# Sheet1.net
KiCad netlist of a schematic drawn in Altium Designer
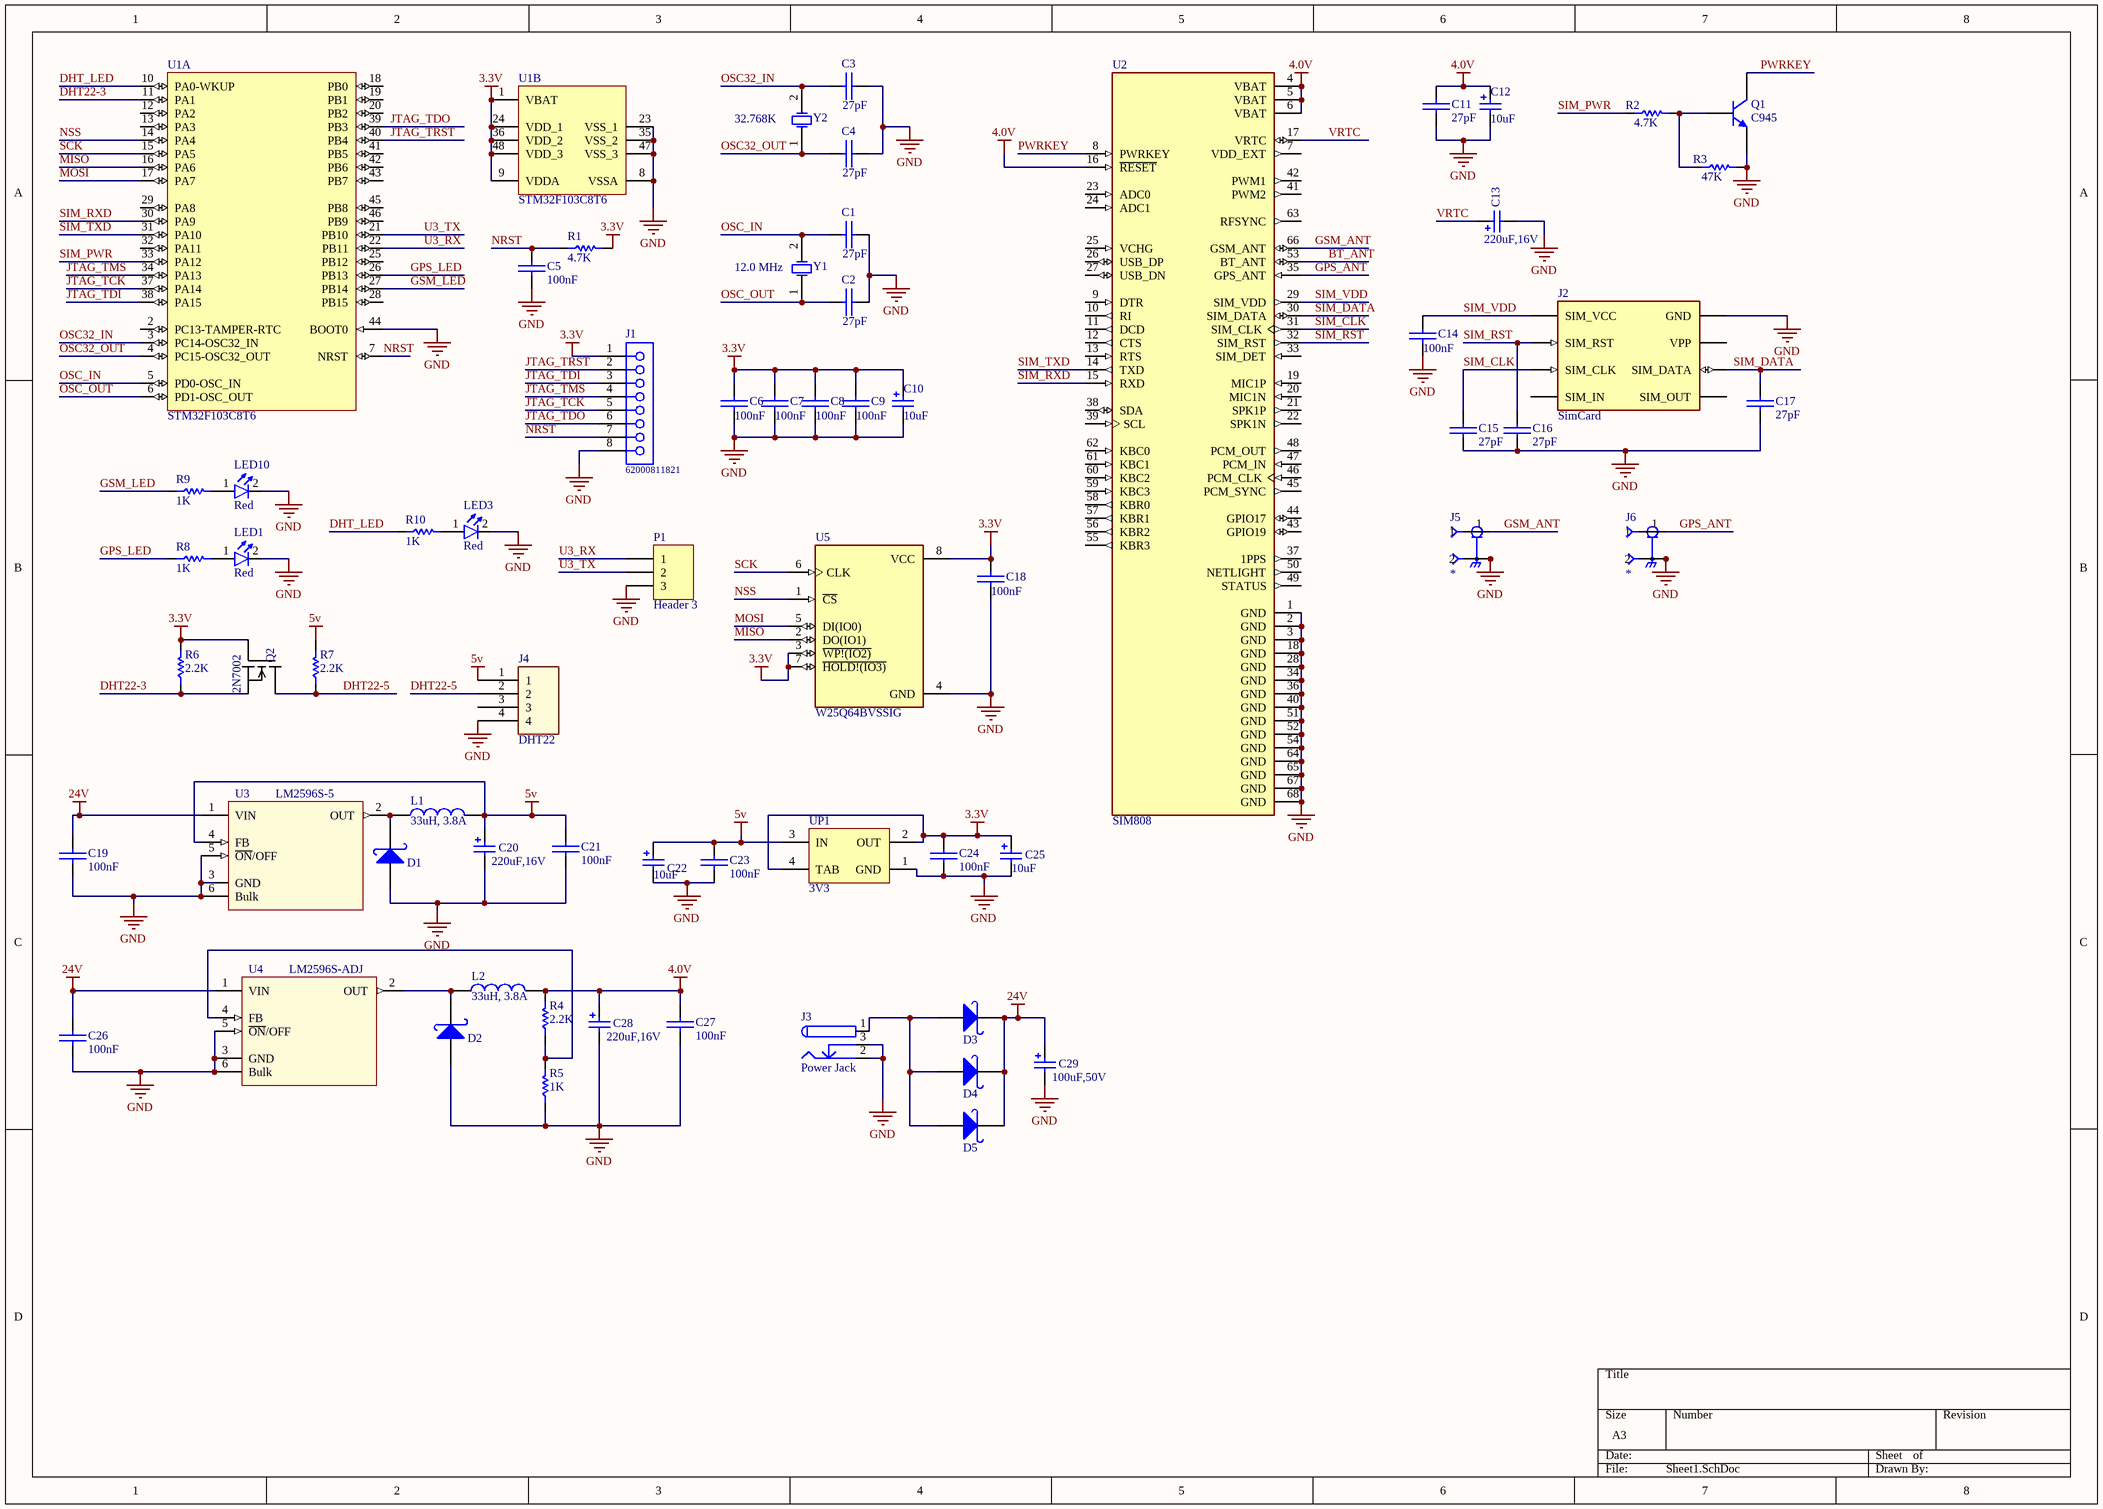
[diagram p0: Sheet1.SchDoc]

(export (version "E")
  (design (tool "Eeschema 10.0.6"))
  (components
    (comp (ref "C1")
      (value "27pF")
      (footprint "SMD_CAP_0805")
      (description "Bipolar Capacitor")
      (fields (field (name "VOLTAGE") "100V") (field (name "DESIGNER") "Saeid Jorablo"))
      (libsource (lib "My_Library") (part "Cap-Bipolar"))
    )
    (comp (ref "C2")
      (value "27pF")
      (footprint "SMD_CAP_0805")
      (description "Bipolar Capacitor")
      (fields (field (name "VOLTAGE") "100V") (field (name "DESIGNER") "Saeid Jorablo"))
      (libsource (lib "My_Library") (part "Cap-Bipolar"))
    )
    (comp (ref "C3")
      (value "27pF")
      (footprint "SMD_CAP_0805")
      (description "Bipolar Capacitor")
      (fields (field (name "VOLTAGE") "100V") (field (name "DESIGNER") "Saeid Jorablo"))
      (libsource (lib "My_Library") (part "Cap-Bipolar"))
    )
    (comp (ref "C4")
      (value "27pF")
      (footprint "SMD_CAP_0805")
      (description "Bipolar Capacitor")
      (fields (field (name "VOLTAGE") "100V") (field (name "DESIGNER") "Saeid Jorablo"))
      (libsource (lib "My_Library") (part "Cap-Bipolar"))
    )
    (comp (ref "C5")
      (value "100nF")
      (footprint "SMD_CAP_0805")
      (description "Bipolar Capacitor")
      (fields (field (name "VOLTAGE") "100V") (field (name "DESIGNER") "Saeid Jorablo"))
      (libsource (lib "My_Library") (part "Cap-Bipolar"))
    )
    (comp (ref "C6")
      (value "100nF")
      (footprint "SMD_CAP_0805")
      (description "Bipolar Capacitor")
      (fields (field (name "VOLTAGE") "100V") (field (name "DESIGNER") "Saeid Jorablo"))
      (libsource (lib "My_Library") (part "Cap-Bipolar"))
    )
    (comp (ref "C7")
      (value "100nF")
      (footprint "SMD_CAP_0805")
      (description "Bipolar Capacitor")
      (fields (field (name "VOLTAGE") "100V") (field (name "DESIGNER") "Saeid Jorablo"))
      (libsource (lib "My_Library") (part "Cap-Bipolar"))
    )
    (comp (ref "C8")
      (value "100nF")
      (footprint "SMD_CAP_0805")
      (description "Bipolar Capacitor")
      (fields (field (name "VOLTAGE") "100V") (field (name "DESIGNER") "Saeid Jorablo"))
      (libsource (lib "My_Library") (part "Cap-Bipolar"))
    )
    (comp (ref "C9")
      (value "100nF")
      (footprint "SMD_CAP_0805")
      (description "Bipolar Capacitor")
      (fields (field (name "VOLTAGE") "100V") (field (name "DESIGNER") "Saeid Jorablo"))
      (libsource (lib "My_Library") (part "Cap-Bipolar"))
    )
    (comp (ref "C10")
      (value "10uF")
      (footprint "WCAP-AS5H_4x5.5")
      (description "WCAP-AS5H SMT Aluminum Electrolytic Capacitors, D4mm x L5.5mm, 22uF, +/-20%, 6.3VDC")
      (fields (field (name "PART NUMBER") "865230140001") (field (name "PUBLISHER") "Wurth Elektronik"))
      (libsource (lib "Altium_WCAP-AS5H (rev19a)") (part "865230140001"))
    )
    (comp (ref "C11")
      (value "27pF")
      (footprint "SMD_CAP_0805")
      (description "Bipolar Capacitor")
      (fields (field (name "VOLTAGE") "100V") (field (name "DESIGNER") "Saeid Jorablo"))
      (libsource (lib "My_Library") (part "Cap-Bipolar"))
    )
    (comp (ref "C12")
      (value "10uF")
      (footprint "WCAP-AS5H_4x5.5")
      (description "WCAP-AS5H SMT Aluminum Electrolytic Capacitors, D4mm x L5.5mm, 22uF, +/-20%, 6.3VDC")
      (fields (field (name "PART NUMBER") "865230140001") (field (name "PUBLISHER") "Wurth Elektronik"))
      (libsource (lib "Altium_WCAP-AS5H (rev19a)") (part "865230140001"))
    )
    (comp (ref "C13")
      (value "220uF,16V")
      (footprint "WCAP-AS5H_6.3x7.7")
      (description "WCAP-AS5H SMT Aluminum Electrolytic Capacitors, D6.3mm x L7.7mm, 100uF, +/-20%, 16VDC")
      (fields (field (name "PART NUMBER") "865230345005") (field (name "PUBLISHER") "Wurth Elektronik"))
      (libsource (lib "Altium_WCAP-AS5H (rev19a)") (part "865230345005"))
    )
    (comp (ref "C14")
      (value "100nF")
      (footprint "SMD_CAP_0805")
      (description "Bipolar Capacitor")
      (fields (field (name "VOLTAGE") "100V") (field (name "DESIGNER") "Saeid Jorablo"))
      (libsource (lib "My_Library") (part "Cap-Bipolar"))
    )
    (comp (ref "C15")
      (value "27pF")
      (footprint "SMD_CAP_0805")
      (description "Bipolar Capacitor")
      (fields (field (name "VOLTAGE") "100V") (field (name "DESIGNER") "Saeid Jorablo"))
      (libsource (lib "My_Library") (part "Cap-Bipolar"))
    )
    (comp (ref "C16")
      (value "27pF")
      (footprint "SMD_CAP_0805")
      (description "Bipolar Capacitor")
      (fields (field (name "VOLTAGE") "100V") (field (name "DESIGNER") "Saeid Jorablo"))
      (libsource (lib "My_Library") (part "Cap-Bipolar"))
    )
    (comp (ref "C17")
      (value "27pF")
      (footprint "SMD_CAP_0805")
      (description "Bipolar Capacitor")
      (fields (field (name "VOLTAGE") "100V") (field (name "DESIGNER") "Saeid Jorablo"))
      (libsource (lib "My_Library") (part "Cap-Bipolar"))
    )
    (comp (ref "C18")
      (value "100nF")
      (footprint "SMD_CAP_0805")
      (description "Bipolar Capacitor")
      (fields (field (name "VOLTAGE") "100V") (field (name "DESIGNER") "Saeid Jorablo"))
      (libsource (lib "My_Library") (part "Cap-Bipolar"))
    )
    (comp (ref "C19")
      (value "100nF")
      (footprint "SMD_CAP_0805")
      (description "Bipolar Capacitor")
      (fields (field (name "VOLTAGE") "100V") (field (name "DESIGNER") "Saeid Jorablo"))
      (libsource (lib "My_Library") (part "Cap-Bipolar"))
    )
    (comp (ref "C20")
      (value "220uF,16V")
      (footprint "WCAP-AS5H_6.3x7.7")
      (description "WCAP-AS5H SMT Aluminum Electrolytic Capacitors, D6.3mm x L7.7mm, 100uF, +/-20%, 16VDC")
      (fields (field (name "PART NUMBER") "865230345005") (field (name "PUBLISHER") "Wurth Elektronik"))
      (libsource (lib "Altium_WCAP-AS5H (rev19a)") (part "865230345005"))
    )
    (comp (ref "C21")
      (value "100nF")
      (footprint "SMD_CAP_0805")
      (description "Bipolar Capacitor")
      (fields (field (name "VOLTAGE") "100V") (field (name "DESIGNER") "Saeid Jorablo"))
      (libsource (lib "My_Library") (part "Cap-Bipolar"))
    )
    (comp (ref "C22")
      (value "10uF")
      (footprint "WCAP-AS5H_4x5.5")
      (description "WCAP-AS5H SMT Aluminum Electrolytic Capacitors, D4mm x L5.5mm, 22uF, +/-20%, 6.3VDC")
      (fields (field (name "PART NUMBER") "865230140001") (field (name "PUBLISHER") "Wurth Elektronik"))
      (libsource (lib "Altium_WCAP-AS5H (rev19a)") (part "865230140001"))
    )
    (comp (ref "C23")
      (value "100nF")
      (footprint "SMD_CAP_0805")
      (description "Bipolar Capacitor")
      (fields (field (name "VOLTAGE") "100V") (field (name "DESIGNER") "Saeid Jorablo"))
      (libsource (lib "My_Library") (part "Cap-Bipolar"))
    )
    (comp (ref "C24")
      (value "100nF")
      (footprint "SMD_CAP_0805")
      (description "Bipolar Capacitor")
      (fields (field (name "VOLTAGE") "100V") (field (name "DESIGNER") "Saeid Jorablo"))
      (libsource (lib "My_Library") (part "Cap-Bipolar"))
    )
    (comp (ref "C25")
      (value "10uF")
      (footprint "WCAP-AS5H_4x5.5")
      (description "WCAP-AS5H SMT Aluminum Electrolytic Capacitors, D4mm x L5.5mm, 22uF, +/-20%, 6.3VDC")
      (fields (field (name "PART NUMBER") "865230140001") (field (name "PUBLISHER") "Wurth Elektronik"))
      (libsource (lib "Altium_WCAP-AS5H (rev19a)") (part "865230140001"))
    )
    (comp (ref "C26")
      (value "100nF")
      (footprint "SMD_CAP_0805")
      (description "Bipolar Capacitor")
      (fields (field (name "VOLTAGE") "100V") (field (name "DESIGNER") "Saeid Jorablo"))
      (libsource (lib "My_Library") (part "Cap-Bipolar"))
    )
    (comp (ref "C27")
      (value "100nF")
      (footprint "SMD_CAP_0805")
      (description "Bipolar Capacitor")
      (fields (field (name "VOLTAGE") "100V") (field (name "DESIGNER") "Saeid Jorablo"))
      (libsource (lib "My_Library") (part "Cap-Bipolar"))
    )
    (comp (ref "C28")
      (value "220uF,16V")
      (footprint "WCAP-AS5H_6.3x7.7")
      (description "WCAP-AS5H SMT Aluminum Electrolytic Capacitors, D6.3mm x L7.7mm, 100uF, +/-20%, 16VDC")
      (fields (field (name "PART NUMBER") "865230345005") (field (name "PUBLISHER") "Wurth Elektronik"))
      (libsource (lib "Altium_WCAP-AS5H (rev19a)") (part "865230345005"))
    )
    (comp (ref "C29")
      (value "100uF,50V")
      (footprint "WCAP-AS5H_8x10.5")
      (description "WCAP-AS5H SMT Aluminum Electrolytic Capacitors, D8mm x L10.5mm, 47uF, +/-20%, 50VDC")
      (fields (field (name "PART NUMBER") "865230653012") (field (name "PUBLISHER") "Wurth Elektronik"))
      (libsource (lib "Altium_WCAP-AS5H (rev19a)") (part "865230653012"))
    )
    (comp (ref "D1")
      (value "1n5822")
      (footprint "Diode 1N4007 SMD")
      (description "Schottky Rectifiers")
      (fields
        (field (name "MANUFACTURER") "ON Semiconductor/Fairchild")
        (field (name "DESIGNER") "Abbas Basereh")
      )
      (libsource (lib "Altium") (part "1N5822 SMD"))
    )
    (comp (ref "D2")
      (value "1n5822")
      (footprint "Diode 1N4007 SMD")
      (description "Schottky Rectifiers")
      (fields
        (field (name "MANUFACTURER") "ON Semiconductor/Fairchild")
        (field (name "DESIGNER") "Abbas Basereh")
      )
      (libsource (lib "Altium") (part "1N5822 SMD"))
    )
    (comp (ref "D3")
      (value "1n5822")
      (footprint "Diode 1N4007 SMD")
      (description "Schottky Rectifiers")
      (fields
        (field (name "MANUFACTURER") "ON Semiconductor/Fairchild")
        (field (name "DESIGNER") "Abbas Basereh")
      )
      (libsource (lib "Altium") (part "1N5822 SMD"))
    )
    (comp (ref "D4")
      (value "1n5822")
      (footprint "Diode 1N4007 SMD")
      (description "Schottky Rectifiers")
      (fields
        (field (name "MANUFACTURER") "ON Semiconductor/Fairchild")
        (field (name "DESIGNER") "Abbas Basereh")
      )
      (libsource (lib "Altium") (part "1N5822 SMD"))
    )
    (comp (ref "D5")
      (value "1n5822")
      (footprint "Diode 1N4007 SMD")
      (description "Schottky Rectifiers")
      (fields
        (field (name "MANUFACTURER") "ON Semiconductor/Fairchild")
        (field (name "DESIGNER") "Abbas Basereh")
      )
      (libsource (lib "Altium") (part "1N5822 SMD"))
    )
    (comp (ref "J1")
      (value "62000811821")
      (footprint "62000811821")
      (description "WR-PHD Socket Header, THT, pitch 2mm, Single Row, Vertical, 8pin")
      (fields (field (name "PUBLISHER") "Wurth Elektronik"))
      (libsource (lib "62000811121_Altium_WR-PHD_rev19a") (part "62000811821"))
    )
    (comp (ref "J2")
      (value "SimCard")
      (footprint "SImCArd")
      (libsource (lib "SimCard_Connector") (part "SimCard"))
    )
    (comp (ref "J3")
      (value "Power Jack")
      (footprint "Power Jack")
      (fields (field (name "DESIGNER") "Saeid Jorablo"))
      (libsource (lib "My_Library") (part "Power Jack"))
    )
    (comp (ref "J4")
      (value "DHT22")
      (footprint "XH-12-Right")
      (libsource (lib "ST-XH-4 pin_right") (part "XH-Connector-4pin-right"))
    )
    (comp (ref "J5")
      (value "221790-1")
      (footprint "TE_221790-1")
      (description "Connector; SMA; PCB; Right Angle; Stainless Steel; 0.6 in.; Beryllium Copper")
      (fields (field (name "MF") "TE Connectivity") (field (name "COMMENT_1") "*"))
      (libsource (lib "SMA_RightAngle") (part "221790-1"))
    )
    (comp (ref "J6")
      (value "221790-1")
      (footprint "TE_221790-1")
      (description "Connector; SMA; PCB; Right Angle; Stainless Steel; 0.6 in.; Beryllium Copper")
      (fields (field (name "MF") "TE Connectivity") (field (name "COMMENT_1") "*"))
      (libsource (lib "SMA_RightAngle") (part "221790-1"))
    )
    (comp (ref "L1")
      (value "33uH, 3.8A")
      (footprint "WE-PD_1210")
      (description "WE-PD SMT Power Inductor, size 1210, 47uH, 3.8A")
      (fields (field (name "PART NUMBER") "7447709470") (field (name "PUBLISHER") "Wurth Elektronik"))
      (libsource (lib "ALTIUM-WE-PD-rev19b") (part "7447709470"))
    )
    (comp (ref "L2")
      (value "33uH, 3.8A")
      (footprint "WE-PD_1210")
      (description "WE-PD SMT Power Inductor, size 1210, 47uH, 3.8A")
      (fields (field (name "PART NUMBER") "7447709470") (field (name "PUBLISHER") "Wurth Elektronik"))
      (libsource (lib "ALTIUM-WE-PD-rev19b") (part "7447709470"))
    )
    (comp (ref "LED1")
      (value "Red")
      (footprint "LED-3mm")
      (description "LED")
      (fields (field (name "COLOR") "Red") (field (name "DESIGNER") "Saeid Jorablo"))
      (libsource (lib "My_Library") (part "LED"))
    )
    (comp (ref "LED3")
      (value "Red")
      (footprint "LED-3mm")
      (description "LED")
      (fields (field (name "COLOR") "Red") (field (name "DESIGNER") "Saeid Jorablo"))
      (libsource (lib "My_Library") (part "LED"))
    )
    (comp (ref "LED10")
      (value "Red")
      (footprint "LED-3mm")
      (description "LED")
      (fields (field (name "COLOR") "Red") (field (name "DESIGNER") "Saeid Jorablo"))
      (libsource (lib "My_Library") (part "LED"))
    )
    (comp (ref "P1")
      (value "Header 3")
      (footprint "HDR1X3")
      (description "Header, 3-Pin")
      (fields (field (name "PUBLISHER") "Altium Limited"))
      (libsource (lib "Altium") (part "Header 3"))
    )
    (comp (ref "Q1")
      (value "C945")
      (footprint "SOT23_N")
      (description "NPN Silicon Epitaxial Planar Transistor")
      (fields (field (name "PUBLISHER") "Abbas Basereh"))
      (libsource (lib "Altium") (part "C945"))
    )
    (comp (ref "Q2")
      (value "2N7002")
      (footprint "*SOT23")
      (description "Transistor NPN Mos 2N7002 SILICONIX miliampere=100 V=60 SOt23")
      (fields (field (name "MF") "STMicroelectronics"))
      (libsource (lib "2N7002") (part "2N7002"))
    )
    (comp (ref "R1")
      (value "4.7K")
      (footprint "RES 0805 (2012X06L)")
      (description "Resistor")
      (fields (field (name "TOLERANCE") "5%") (field (name "POWER") "1/8 W"))
      (libsource (lib "My_Library") (part "Resistor"))
    )
    (comp (ref "R2")
      (value "4.7K")
      (footprint "RES 0805 (2012X06L)")
      (description "Resistor")
      (fields (field (name "TOLERANCE") "5%") (field (name "POWER") "1/8 W"))
      (libsource (lib "My_Library") (part "Resistor"))
    )
    (comp (ref "R3")
      (value "47K")
      (footprint "RES 0805 (2012X06L)")
      (description "Resistor")
      (fields (field (name "TOLERANCE") "5%") (field (name "POWER") "1/8 W"))
      (libsource (lib "My_Library") (part "Resistor"))
    )
    (comp (ref "R4")
      (value "2.2K")
      (footprint "RES 0805 (2012X06L)")
      (description "Resistor")
      (fields (field (name "TOLERANCE") "5%") (field (name "POWER") "1/8 W"))
      (libsource (lib "My_Library") (part "Resistor"))
    )
    (comp (ref "R5")
      (value "1K")
      (footprint "RES 0805 (2012X06L)")
      (description "Resistor")
      (fields (field (name "TOLERANCE") "5%") (field (name "POWER") "1/8 W"))
      (libsource (lib "My_Library") (part "Resistor"))
    )
    (comp (ref "R6")
      (value "2.2K")
      (footprint "RES 0805 (2012X06L)")
      (description "Resistor")
      (fields (field (name "TOLERANCE") "5%") (field (name "POWER") "1/8 W"))
      (libsource (lib "My_Library") (part "Resistor"))
    )
    (comp (ref "R7")
      (value "2.2K")
      (footprint "RES 0805 (2012X06L)")
      (description "Resistor")
      (fields (field (name "TOLERANCE") "5%") (field (name "POWER") "1/8 W"))
      (libsource (lib "My_Library") (part "Resistor"))
    )
    (comp (ref "R8")
      (value "1K")
      (footprint "RES 0805 (2012X06L)")
      (description "Resistor")
      (fields (field (name "TOLERANCE") "5%") (field (name "POWER") "1/8 W"))
      (libsource (lib "My_Library") (part "Resistor"))
    )
    (comp (ref "R9")
      (value "1K")
      (footprint "RES 0805 (2012X06L)")
      (description "Resistor")
      (fields (field (name "TOLERANCE") "5%") (field (name "POWER") "1/8 W"))
      (libsource (lib "My_Library") (part "Resistor"))
    )
    (comp (ref "R10")
      (value "1K")
      (footprint "RES 0805 (2012X06L)")
      (description "Resistor")
      (fields (field (name "TOLERANCE") "5%") (field (name "POWER") "1/8 W"))
      (libsource (lib "My_Library") (part "Resistor"))
    )
    (comp (ref "U1")
      (value "STM32F103C8T6")
      (footprint "STM-LQFP48_N")
      (libsource (lib "STMicroelectronics STM32 F1") (part "STM32F103C8T6"))
    )
    (comp (ref "U2")
      (value "SIM808")
      (footprint "XCVR_SIM808")
      (description "SIM808 GPS, GPRS/GSM RF Arduino Platform Evaluation Expansion Board")
      (fields (field (name "MF") "Adafruit Industries"))
      (libsource (lib "SIM_808") (part "SIM808"))
    )
    (comp (ref "U3")
      (value "LM2596S-5")
      (footprint "*TO170P1435X465-6N")
      (fields (field (name "MF") "Texas Instruments"))
      (libsource (lib "LM2596S-3.3") (part "LM2596S-3.3"))
    )
    (comp (ref "U4")
      (value "LM2596S-ADJ")
      (footprint "*TO170P1435X465-6N")
      (fields (field (name "MP") "LM2596S-5") (field (name "MF") "Texas Instruments"))
      (libsource (lib "LM2596S-3.3") (part "LM2596S-3.3"))
    )
    (comp (ref "U5")
      (value "W25Q64BVSSIG")
      (footprint "SOIC127P790X216-8N")
      (description "FLASH - NOR Memory IC 64Mb _8M x 8_ SPI 80MHz 8-SOIC")
      (fields (field (name "MF") "Winbond Electronics"))
      (libsource (lib "W25Q64FV") (part "W25Q64BVSSIG"))
    )
    (comp (ref "UP1")
      (value "3V3")
      (footprint "SOT223")
      (description "x.x Volt, 800mA Low-Dropout Linear Regulator, 4-pin SOT-223")
      (fields (field (name "DESIGNER") "Ali Hafizi"))
      (libsource (lib "Altium") (part "AMS1117-x.x"))
    )
    (comp (ref "Y1")
      (value "12.0 MHz")
      (footprint "Crystal SMD")
      (description "XTAL Crystal")
      (libsource (lib "My_Library") (part "XTAL"))
    )
    (comp (ref "Y2")
      (value "32.768K")
      (footprint "XTAL RTC")
      (description "XTAL Crystal")
      (libsource (lib "My_Library") (part "XTAL"))
    )
  )
  (nets
    (net (code "1") (name "/BT_ANT") (class "Default")
      (node (ref "U2") (pin "53") (pinfunction "BT_ANT_53") (pintype "bidirectional"))
    )
    (net (code "2") (name "/DHT22-3") (class "Default")
      (node (ref "Q2") (pin "2") (pinfunction "S_2") (pintype "passive"))
      (node (ref "R6") (pin "1") (pinfunction "1_1") (pintype "passive"))
      (node (ref "U1") (pin "11") (pinfunction "PA1_11") (pintype "bidirectional"))
    )
    (net (code "3") (name "/DHT22-5") (class "Default")
      (node (ref "J4") (pin "2") (pinfunction "2_2") (pintype "passive"))
      (node (ref "Q2") (pin "3") (pinfunction "D_3") (pintype "passive"))
      (node (ref "R7") (pin "1") (pinfunction "1_1") (pintype "passive"))
    )
    (net (code "4") (name "/DHT_LED") (class "Default")
      (node (ref "R10") (pin "1") (pinfunction "1_1") (pintype "passive"))
      (node (ref "U1") (pin "10") (pinfunction "PA0-WKUP_10") (pintype "bidirectional"))
    )
    (net (code "5") (name "/GPS_ANT") (class "Default")
      (node (ref "J6") (pin "1") (pinfunction "1_1") (pintype "passive"))
      (node (ref "U2") (pin "35") (pinfunction "GPS_ANT_35") (pintype "input"))
    )
    (net (code "6") (name "/GPS_LED") (class "Default")
      (node (ref "R8") (pin "1") (pinfunction "1_1") (pintype "passive"))
      (node (ref "U1") (pin "26") (pinfunction "PB13_26") (pintype "bidirectional"))
    )
    (net (code "7") (name "/GSM_ANT") (class "Default")
      (node (ref "J5") (pin "1") (pinfunction "1_1") (pintype "passive"))
      (node (ref "U2") (pin "66") (pinfunction "GSM_ANT_66") (pintype "bidirectional"))
    )
    (net (code "8") (name "/GSM_LED") (class "Default")
      (node (ref "R9") (pin "1") (pinfunction "1_1") (pintype "passive"))
      (node (ref "U1") (pin "27") (pinfunction "PB14_27") (pintype "bidirectional"))
    )
    (net (code "9") (name "/JTAG_TCK") (class "Default")
      (node (ref "J1") (pin "5") (pinfunction "5_5") (pintype "passive"))
      (node (ref "U1") (pin "37") (pinfunction "PA14_37") (pintype "bidirectional"))
    )
    (net (code "10") (name "/JTAG_TDI") (class "Default")
      (node (ref "J1") (pin "3") (pinfunction "3_3") (pintype "passive"))
      (node (ref "U1") (pin "38") (pinfunction "PA15_38") (pintype "bidirectional"))
    )
    (net (code "11") (name "/JTAG_TDO") (class "Default")
      (node (ref "J1") (pin "6") (pinfunction "6_6") (pintype "passive"))
      (node (ref "U1") (pin "39") (pinfunction "PB3_39") (pintype "bidirectional"))
    )
    (net (code "12") (name "/JTAG_TMS") (class "Default")
      (node (ref "J1") (pin "4") (pinfunction "4_4") (pintype "passive"))
      (node (ref "U1") (pin "34") (pinfunction "PA13_34") (pintype "bidirectional"))
    )
    (net (code "13") (name "/JTAG_TRST") (class "Default")
      (node (ref "J1") (pin "2") (pinfunction "2_2") (pintype "passive"))
      (node (ref "U1") (pin "40") (pinfunction "PB4_40") (pintype "bidirectional"))
    )
    (net (code "14") (name "/MISO") (class "Default")
      (node (ref "U1") (pin "16") (pinfunction "PA6_16") (pintype "bidirectional"))
      (node (ref "U5") (pin "2") (pinfunction "DO(IO1)_2") (pintype "bidirectional"))
    )
    (net (code "15") (name "/MOSI") (class "Default")
      (node (ref "U1") (pin "17") (pinfunction "PA7_17") (pintype "bidirectional"))
      (node (ref "U5") (pin "5") (pinfunction "DI(IO0)_5") (pintype "bidirectional"))
    )
    (net (code "16") (name "/NRST") (class "Default")
      (node (ref "C5") (pin "1") (pinfunction "+_1") (pintype "passive"))
      (node (ref "J1") (pin "7") (pinfunction "7_7") (pintype "passive"))
      (node (ref "R1") (pin "1") (pinfunction "1_1") (pintype "passive"))
      (node (ref "U1") (pin "7") (pinfunction "NRST_7") (pintype "bidirectional"))
    )
    (net (code "17") (name "/NSS") (class "Default")
      (node (ref "U1") (pin "14") (pinfunction "PA4_14") (pintype "bidirectional"))
      (node (ref "U5") (pin "1") (pinfunction "~{CS}_1") (pintype "input"))
    )
    (net (code "18") (name "/OSC32_IN") (class "Default")
      (node (ref "C3") (pin "1") (pinfunction "+_1") (pintype "passive"))
      (node (ref "U1") (pin "3") (pinfunction "PC14-OSC32_IN_3") (pintype "bidirectional"))
      (node (ref "Y2") (pin "2") (pinfunction "OSC2_2") (pintype "passive"))
    )
    (net (code "19") (name "/OSC32_OUT") (class "Default")
      (node (ref "C4") (pin "1") (pinfunction "+_1") (pintype "passive"))
      (node (ref "U1") (pin "4") (pinfunction "PC15-OSC32_OUT_4") (pintype "bidirectional"))
      (node (ref "Y2") (pin "1") (pinfunction "OSC1_1") (pintype "passive"))
    )
    (net (code "20") (name "/OSC_IN") (class "Default")
      (node (ref "C1") (pin "1") (pinfunction "+_1") (pintype "passive"))
      (node (ref "U1") (pin "5") (pinfunction "PD0-OSC_IN_5") (pintype "bidirectional"))
      (node (ref "Y1") (pin "2") (pinfunction "OSC2_2") (pintype "passive"))
    )
    (net (code "21") (name "/OSC_OUT") (class "Default")
      (node (ref "C2") (pin "1") (pinfunction "+_1") (pintype "passive"))
      (node (ref "U1") (pin "6") (pinfunction "PD1-OSC_OUT_6") (pintype "bidirectional"))
      (node (ref "Y1") (pin "1") (pinfunction "OSC1_1") (pintype "passive"))
    )
    (net (code "22") (name "/PWRKEY") (class "Default")
      (node (ref "Q1") (pin "3") (pinfunction "C_3") (pintype "passive"))
      (node (ref "U2") (pin "8") (pinfunction "PWRKEY_8") (pintype "input"))
    )
    (net (code "23") (name "/SCK") (class "Default")
      (node (ref "U1") (pin "15") (pinfunction "PA5_15") (pintype "bidirectional"))
      (node (ref "U5") (pin "6") (pinfunction "CLK_6") (pintype "input"))
    )
    (net (code "24") (name "/SIM_CLK") (class "Default")
      (node (ref "C15") (pin "2") (pinfunction "-_2") (pintype "passive"))
      (node (ref "J2") (pin "C3") (pinfunction "SIM_CLK_C3") (pintype "input"))
      (node (ref "U2") (pin "31") (pinfunction "SIM_CLK_31") (pintype "output"))
    )
    (net (code "25") (name "/SIM_DATA") (class "Default")
      (node (ref "C17") (pin "2") (pinfunction "-_2") (pintype "passive"))
      (node (ref "J2") (pin "C7") (pinfunction "SIM_DATA_C7") (pintype "bidirectional"))
      (node (ref "U2") (pin "30") (pinfunction "SIM_DATA_30") (pintype "bidirectional"))
    )
    (net (code "26") (name "/SIM_PWR") (class "Default")
      (node (ref "R2") (pin "1") (pinfunction "1_1") (pintype "passive"))
      (node (ref "U1") (pin "33") (pinfunction "PA12_33") (pintype "bidirectional"))
    )
    (net (code "27") (name "/SIM_RST") (class "Default")
      (node (ref "C16") (pin "2") (pinfunction "-_2") (pintype "passive"))
      (node (ref "J2") (pin "C2") (pinfunction "SIM_RST_C2") (pintype "input"))
      (node (ref "U2") (pin "32") (pinfunction "SIM_RST_32") (pintype "output"))
    )
    (net (code "28") (name "/SIM_RXD") (class "Default")
      (node (ref "U1") (pin "30") (pinfunction "PA9_30") (pintype "bidirectional"))
      (node (ref "U2") (pin "15") (pinfunction "RXD_15") (pintype "input"))
    )
    (net (code "29") (name "/SIM_TXD") (class "Default")
      (node (ref "U1") (pin "31") (pinfunction "PA10_31") (pintype "bidirectional"))
      (node (ref "U2") (pin "14") (pinfunction "TXD_14") (pintype "output"))
    )
    (net (code "30") (name "/SIM_VDD") (class "Default")
      (node (ref "C14") (pin "1") (pinfunction "+_1") (pintype "passive"))
      (node (ref "J2") (pin "C1") (pinfunction "SIM_VCC_C1") (pintype "power_in"))
      (node (ref "U2") (pin "29") (pinfunction "SIM_VDD_29") (pintype "output"))
    )
    (net (code "31") (name "/U3_RX") (class "Default")
      (node (ref "P1") (pin "1") (pinfunction "1_1") (pintype "passive"))
      (node (ref "U1") (pin "22") (pinfunction "PB11_22") (pintype "bidirectional"))
    )
    (net (code "32") (name "/U3_TX") (class "Default")
      (node (ref "P1") (pin "2") (pinfunction "2_2") (pintype "passive"))
      (node (ref "U1") (pin "21") (pinfunction "PB10_21") (pintype "bidirectional"))
    )
    (net (code "33") (name "/VRTC") (class "Default")
      (node (ref "C13") (pin "2") (pinfunction "P_2") (pintype "passive"))
      (node (ref "U2") (pin "17") (pinfunction "VRTC_17") (pintype "bidirectional"))
    )
    (net (code "34") (name "3.3V") (class "Default")
      (node (ref "C10") (pin "2") (pinfunction "P_2") (pintype "passive"))
      (node (ref "C18") (pin "1") (pinfunction "+_1") (pintype "passive"))
      (node (ref "C24") (pin "1") (pinfunction "+_1") (pintype "passive"))
      (node (ref "C25") (pin "2") (pinfunction "P_2") (pintype "passive"))
      (node (ref "C6") (pin "1") (pinfunction "+_1") (pintype "passive"))
      (node (ref "C7") (pin "1") (pinfunction "+_1") (pintype "passive"))
      (node (ref "C8") (pin "1") (pinfunction "+_1") (pintype "passive"))
      (node (ref "C9") (pin "1") (pinfunction "+_1") (pintype "passive"))
      (node (ref "J1") (pin "1") (pinfunction "1_1") (pintype "passive"))
      (node (ref "Q2") (pin "1") (pinfunction "G_1") (pintype "passive"))
      (node (ref "R1") (pin "2") (pinfunction "2_2") (pintype "passive"))
      (node (ref "R6") (pin "2") (pinfunction "2_2") (pintype "passive"))
      (node (ref "U1") (pin "1") (pinfunction "VBAT_1") (pintype "power_in"))
      (node (ref "U1") (pin "24") (pinfunction "VDD_1_24") (pintype "power_in"))
      (node (ref "U1") (pin "36") (pinfunction "VDD_2_36") (pintype "power_in"))
      (node (ref "U1") (pin "48") (pinfunction "VDD_3_48") (pintype "power_in"))
      (node (ref "U1") (pin "9") (pinfunction "VDDA_9") (pintype "power_in"))
      (node (ref "U5") (pin "3") (pinfunction "~{WP!(IO2)}_3") (pintype "bidirectional"))
      (node (ref "U5") (pin "7") (pinfunction "~{HOLD!(IO3)}_7") (pintype "bidirectional"))
      (node (ref "U5") (pin "8") (pinfunction "VCC_8") (pintype "power_in"))
      (node (ref "UP1") (pin "2") (pinfunction "OUT_2") (pintype "power_in"))
      (node (ref "UP1") (pin "4") (pinfunction "TAB_4") (pintype "power_in"))
    )
    (net (code "35") (name "4.0V") (class "Default")
      (node (ref "C11") (pin "2") (pinfunction "-_2") (pintype "passive"))
      (node (ref "C12") (pin "2") (pinfunction "P_2") (pintype "passive"))
      (node (ref "C27") (pin "1") (pinfunction "+_1") (pintype "passive"))
      (node (ref "C28") (pin "2") (pinfunction "P_2") (pintype "passive"))
      (node (ref "L2") (pin "2") (pinfunction "2_2") (pintype "passive"))
      (node (ref "R4") (pin "2") (pinfunction "2_2") (pintype "passive"))
      (node (ref "U2") (pin "16") (pinfunction "~{RESET}_16") (pintype "input"))
      (node (ref "U2") (pin "4") (pinfunction "VBAT_4") (pintype "power_in"))
      (node (ref "U2") (pin "5") (pinfunction "VBAT_5") (pintype "power_in"))
      (node (ref "U2") (pin "6") (pinfunction "VBAT_6") (pintype "power_in"))
    )
    (net (code "36") (name "5v") (class "Default")
      (node (ref "C20") (pin "2") (pinfunction "P_2") (pintype "passive"))
      (node (ref "C21") (pin "1") (pinfunction "+_1") (pintype "passive"))
      (node (ref "C22") (pin "2") (pinfunction "P_2") (pintype "passive"))
      (node (ref "C23") (pin "1") (pinfunction "+_1") (pintype "passive"))
      (node (ref "J4") (pin "1") (pinfunction "1_1") (pintype "passive"))
      (node (ref "L1") (pin "2") (pinfunction "2_2") (pintype "passive"))
      (node (ref "R7") (pin "2") (pinfunction "2_2") (pintype "passive"))
      (node (ref "U3") (pin "4") (pinfunction "FB_4") (pintype "input"))
      (node (ref "UP1") (pin "3") (pinfunction "IN_3") (pintype "power_in"))
    )
    (net (code "37") (name "24V") (class "Default")
      (node (ref "C19") (pin "1") (pinfunction "+_1") (pintype "passive"))
      (node (ref "C26") (pin "1") (pinfunction "+_1") (pintype "passive"))
      (node (ref "C29") (pin "2") (pinfunction "P_2") (pintype "passive"))
      (node (ref "D3") (pin "2") (pinfunction "K_2") (pintype "passive"))
      (node (ref "D4") (pin "2") (pinfunction "K_2") (pintype "passive"))
      (node (ref "D5") (pin "2") (pinfunction "K_2") (pintype "passive"))
      (node (ref "U3") (pin "1") (pinfunction "VIN_1") (pintype "power_in"))
      (node (ref "U4") (pin "1") (pinfunction "VIN_1") (pintype "power_in"))
    )
    (net (code "38") (name "GND") (class "Default")
      (node (ref "C1") (pin "2") (pinfunction "-_2") (pintype "passive"))
      (node (ref "C10") (pin "1") (pinfunction "N_1") (pintype "passive"))
      (node (ref "C11") (pin "1") (pinfunction "+_1") (pintype "passive"))
      (node (ref "C12") (pin "1") (pinfunction "N_1") (pintype "passive"))
      (node (ref "C13") (pin "1") (pinfunction "N_1") (pintype "passive"))
      (node (ref "C14") (pin "2") (pinfunction "-_2") (pintype "passive"))
      (node (ref "C15") (pin "1") (pinfunction "+_1") (pintype "passive"))
      (node (ref "C16") (pin "1") (pinfunction "+_1") (pintype "passive"))
      (node (ref "C17") (pin "1") (pinfunction "+_1") (pintype "passive"))
      (node (ref "C18") (pin "2") (pinfunction "-_2") (pintype "passive"))
      (node (ref "C19") (pin "2") (pinfunction "-_2") (pintype "passive"))
      (node (ref "C2") (pin "2") (pinfunction "-_2") (pintype "passive"))
      (node (ref "C20") (pin "1") (pinfunction "N_1") (pintype "passive"))
      (node (ref "C21") (pin "2") (pinfunction "-_2") (pintype "passive"))
      (node (ref "C22") (pin "1") (pinfunction "N_1") (pintype "passive"))
      (node (ref "C23") (pin "2") (pinfunction "-_2") (pintype "passive"))
      (node (ref "C24") (pin "2") (pinfunction "-_2") (pintype "passive"))
      (node (ref "C25") (pin "1") (pinfunction "N_1") (pintype "passive"))
      (node (ref "C26") (pin "2") (pinfunction "-_2") (pintype "passive"))
      (node (ref "C27") (pin "2") (pinfunction "-_2") (pintype "passive"))
      (node (ref "C28") (pin "1") (pinfunction "N_1") (pintype "passive"))
      (node (ref "C29") (pin "1") (pinfunction "N_1") (pintype "passive"))
      (node (ref "C3") (pin "2") (pinfunction "-_2") (pintype "passive"))
      (node (ref "C4") (pin "2") (pinfunction "-_2") (pintype "passive"))
      (node (ref "C5") (pin "2") (pinfunction "-_2") (pintype "passive"))
      (node (ref "C6") (pin "2") (pinfunction "-_2") (pintype "passive"))
      (node (ref "C7") (pin "2") (pinfunction "-_2") (pintype "passive"))
      (node (ref "C8") (pin "2") (pinfunction "-_2") (pintype "passive"))
      (node (ref "C9") (pin "2") (pinfunction "-_2") (pintype "passive"))
      (node (ref "D1") (pin "1") (pinfunction "A_1") (pintype "passive"))
      (node (ref "D2") (pin "1") (pinfunction "A_1") (pintype "passive"))
      (node (ref "J1") (pin "8") (pinfunction "8_8") (pintype "passive"))
      (node (ref "J2") (pin "C5") (pinfunction "GND_C5") (pintype "power_in"))
      (node (ref "J3") (pin "2") (pinfunction "2_2") (pintype "power_in"))
      (node (ref "J3") (pin "3") (pinfunction "3_3") (pintype "power_in"))
      (node (ref "J4") (pin "4") (pinfunction "4_4") (pintype "passive"))
      (node (ref "J5") (pin "2") (pinfunction "2_2") (pintype "passive"))
      (node (ref "J5") (pin "3") (pinfunction "2_3") (pintype "passive"))
      (node (ref "J5") (pin "4") (pinfunction "2_4") (pintype "passive"))
      (node (ref "J5") (pin "5") (pinfunction "2_5") (pintype "passive"))
      (node (ref "J6") (pin "2") (pinfunction "2_2") (pintype "passive"))
      (node (ref "J6") (pin "3") (pinfunction "2_3") (pintype "passive"))
      (node (ref "J6") (pin "4") (pinfunction "2_4") (pintype "passive"))
      (node (ref "J6") (pin "5") (pinfunction "2_5") (pintype "passive"))
      (node (ref "LED1") (pin "2") (pinfunction "K_2") (pintype "passive"))
      (node (ref "LED10") (pin "2") (pinfunction "K_2") (pintype "passive"))
      (node (ref "LED3") (pin "2") (pinfunction "K_2") (pintype "passive"))
      (node (ref "P1") (pin "3") (pinfunction "3_3") (pintype "passive"))
      (node (ref "Q1") (pin "2") (pinfunction "E_2") (pintype "passive"))
      (node (ref "R3") (pin "2") (pinfunction "2_2") (pintype "passive"))
      (node (ref "R5") (pin "1") (pinfunction "1_1") (pintype "passive"))
      (node (ref "U1") (pin "23") (pinfunction "VSS_1_23") (pintype "power_in"))
      (node (ref "U1") (pin "35") (pinfunction "VSS_2_35") (pintype "power_in"))
      (node (ref "U1") (pin "44") (pinfunction "BOOT0_44") (pintype "input"))
      (node (ref "U1") (pin "47") (pinfunction "VSS_3_47") (pintype "power_in"))
      (node (ref "U1") (pin "8") (pinfunction "VSSA_8") (pintype "power_in"))
      (node (ref "U2") (pin "1") (pinfunction "GND_1") (pintype "power_in"))
      (node (ref "U2") (pin "18") (pinfunction "GND_18") (pintype "power_in"))
      (node (ref "U2") (pin "2") (pinfunction "GND_2") (pintype "power_in"))
      (node (ref "U2") (pin "28") (pinfunction "GND_28") (pintype "power_in"))
      (node (ref "U2") (pin "3") (pinfunction "GND_3") (pintype "power_in"))
      (node (ref "U2") (pin "34") (pinfunction "GND_34") (pintype "power_in"))
      (node (ref "U2") (pin "36") (pinfunction "GND_36") (pintype "power_in"))
      (node (ref "U2") (pin "40") (pinfunction "GND_40") (pintype "power_in"))
      (node (ref "U2") (pin "51") (pinfunction "GND_51") (pintype "power_in"))
      (node (ref "U2") (pin "52") (pinfunction "GND_52") (pintype "power_in"))
      (node (ref "U2") (pin "54") (pinfunction "GND_54") (pintype "power_in"))
      (node (ref "U2") (pin "64") (pinfunction "GND_64") (pintype "power_in"))
      (node (ref "U2") (pin "65") (pinfunction "GND_65") (pintype "power_in"))
      (node (ref "U2") (pin "67") (pinfunction "GND_67") (pintype "power_in"))
      (node (ref "U2") (pin "68") (pinfunction "GND_68") (pintype "power_in"))
      (node (ref "U3") (pin "3") (pinfunction "GND_3") (pintype "passive"))
      (node (ref "U3") (pin "5") (pinfunction "~{ON}/OFF_5") (pintype "input"))
      (node (ref "U3") (pin "6") (pinfunction "Bulk_6") (pintype "passive"))
      (node (ref "U4") (pin "3") (pinfunction "GND_3") (pintype "passive"))
      (node (ref "U4") (pin "5") (pinfunction "~{ON}/OFF_5") (pintype "input"))
      (node (ref "U4") (pin "6") (pinfunction "Bulk_6") (pintype "passive"))
      (node (ref "U5") (pin "4") (pinfunction "GND_4") (pintype "power_in"))
      (node (ref "UP1") (pin "1") (pinfunction "GND_1") (pintype "power_in"))
    )
    (net (code "39") (name "Net-(D1-K)") (class "Default")
      (node (ref "D1") (pin "2") (pinfunction "K_2") (pintype "passive"))
      (node (ref "L1") (pin "1") (pinfunction "1_1") (pintype "passive"))
      (node (ref "U3") (pin "2") (pinfunction "OUT_2") (pintype "output"))
    )
    (net (code "40") (name "Net-(D2-K)") (class "Default")
      (node (ref "D2") (pin "2") (pinfunction "K_2") (pintype "passive"))
      (node (ref "L2") (pin "1") (pinfunction "1_1") (pintype "passive"))
      (node (ref "U4") (pin "2") (pinfunction "OUT_2") (pintype "output"))
    )
    (net (code "41") (name "Net-(D3-A)") (class "Default")
      (node (ref "D3") (pin "1") (pinfunction "A_1") (pintype "passive"))
      (node (ref "D4") (pin "1") (pinfunction "A_1") (pintype "passive"))
      (node (ref "D5") (pin "1") (pinfunction "A_1") (pintype "passive"))
      (node (ref "J3") (pin "1") (pinfunction "1_1") (pintype "power_in"))
    )
    (net (code "42") (name "Net-(LED1-A)") (class "Default")
      (node (ref "LED1") (pin "1") (pinfunction "A_1") (pintype "passive"))
      (node (ref "R8") (pin "2") (pinfunction "2_2") (pintype "passive"))
    )
    (net (code "43") (name "Net-(LED3-A)") (class "Default")
      (node (ref "LED3") (pin "1") (pinfunction "A_1") (pintype "passive"))
      (node (ref "R10") (pin "2") (pinfunction "2_2") (pintype "passive"))
    )
    (net (code "44") (name "Net-(LED10-A)") (class "Default")
      (node (ref "LED10") (pin "1") (pinfunction "A_1") (pintype "passive"))
      (node (ref "R9") (pin "2") (pinfunction "2_2") (pintype "passive"))
    )
    (net (code "45") (name "Net-(Q1-B)") (class "Default")
      (node (ref "Q1") (pin "1") (pinfunction "B_1") (pintype "passive"))
      (node (ref "R2") (pin "2") (pinfunction "2_2") (pintype "passive"))
      (node (ref "R3") (pin "1") (pinfunction "1_1") (pintype "passive"))
    )
    (net (code "46") (name "Net-(U4-FB)") (class "Default")
      (node (ref "R4") (pin "1") (pinfunction "1_1") (pintype "passive"))
      (node (ref "R5") (pin "2") (pinfunction "2_2") (pintype "passive"))
      (node (ref "U4") (pin "4") (pinfunction "FB_4") (pintype "input"))
    )
    (net (code "47") (name "unconnected-(J2-SIM_IN-PadC4)") (class "Default")
      (node (ref "J2") (pin "C4") (pinfunction "SIM_IN_C4") (pintype "passive"))
    )
    (net (code "48") (name "unconnected-(J2-SIM_OUT-PadC8)") (class "Default")
      (node (ref "J2") (pin "C8") (pinfunction "SIM_OUT_C8") (pintype "passive"))
    )
    (net (code "49") (name "unconnected-(J2-VPP-PadC6)") (class "Default")
      (node (ref "J2") (pin "C6") (pinfunction "VPP_C6") (pintype "passive"))
    )
    (net (code "50") (name "unconnected-(J4-Pad3)") (class "Default")
      (node (ref "J4") (pin "3") (pinfunction "3_3") (pintype "passive"))
    )
    (net (code "51") (name "unconnected-(U1A-PA2-Pad12)") (class "Default")
      (node (ref "U1") (pin "12") (pinfunction "PA2_12") (pintype "bidirectional"))
    )
    (net (code "52") (name "unconnected-(U1A-PA3-Pad13)") (class "Default")
      (node (ref "U1") (pin "13") (pinfunction "PA3_13") (pintype "bidirectional"))
    )
    (net (code "53") (name "unconnected-(U1A-PA8-Pad29)") (class "Default")
      (node (ref "U1") (pin "29") (pinfunction "PA8_29") (pintype "bidirectional"))
    )
    (net (code "54") (name "unconnected-(U1A-PA11-Pad32)") (class "Default")
      (node (ref "U1") (pin "32") (pinfunction "PA11_32") (pintype "bidirectional"))
    )
    (net (code "55") (name "unconnected-(U1A-PB0-Pad18)") (class "Default")
      (node (ref "U1") (pin "18") (pinfunction "PB0_18") (pintype "bidirectional"))
    )
    (net (code "56") (name "unconnected-(U1A-PB1-Pad19)") (class "Default")
      (node (ref "U1") (pin "19") (pinfunction "PB1_19") (pintype "bidirectional"))
    )
    (net (code "57") (name "unconnected-(U1A-PB2-Pad20)") (class "Default")
      (node (ref "U1") (pin "20") (pinfunction "PB2_20") (pintype "bidirectional"))
    )
    (net (code "58") (name "unconnected-(U1A-PB5-Pad41)") (class "Default")
      (node (ref "U1") (pin "41") (pinfunction "PB5_41") (pintype "bidirectional"))
    )
    (net (code "59") (name "unconnected-(U1A-PB6-Pad42)") (class "Default")
      (node (ref "U1") (pin "42") (pinfunction "PB6_42") (pintype "bidirectional"))
    )
    (net (code "60") (name "unconnected-(U1A-PB7-Pad43)") (class "Default")
      (node (ref "U1") (pin "43") (pinfunction "PB7_43") (pintype "bidirectional"))
    )
    (net (code "61") (name "unconnected-(U1A-PB8-Pad45)") (class "Default")
      (node (ref "U1") (pin "45") (pinfunction "PB8_45") (pintype "bidirectional"))
    )
    (net (code "62") (name "unconnected-(U1A-PB9-Pad46)") (class "Default")
      (node (ref "U1") (pin "46") (pinfunction "PB9_46") (pintype "bidirectional"))
    )
    (net (code "63") (name "unconnected-(U1A-PB12-Pad25)") (class "Default")
      (node (ref "U1") (pin "25") (pinfunction "PB12_25") (pintype "bidirectional"))
    )
    (net (code "64") (name "unconnected-(U1A-PB15-Pad28)") (class "Default")
      (node (ref "U1") (pin "28") (pinfunction "PB15_28") (pintype "bidirectional"))
    )
    (net (code "65") (name "unconnected-(U1A-PC13-TAMPER-RTC-Pad2)") (class "Default")
      (node (ref "U1") (pin "2") (pinfunction "PC13-TAMPER-RTC_2") (pintype "bidirectional"))
    )
    (net (code "66") (name "unconnected-(U2-1PPS-Pad37)") (class "Default")
      (node (ref "U2") (pin "37") (pinfunction "1PPS_37") (pintype "output"))
    )
    (net (code "67") (name "unconnected-(U2-ADC0-Pad23)") (class "Default")
      (node (ref "U2") (pin "23") (pinfunction "ADC0_23") (pintype "input"))
    )
    (net (code "68") (name "unconnected-(U2-ADC1-Pad24)") (class "Default")
      (node (ref "U2") (pin "24") (pinfunction "ADC1_24") (pintype "input"))
    )
    (net (code "69") (name "unconnected-(U2-CTS-Pad12)") (class "Default")
      (node (ref "U2") (pin "12") (pinfunction "CTS_12") (pintype "output"))
    )
    (net (code "70") (name "unconnected-(U2-DCD-Pad11)") (class "Default")
      (node (ref "U2") (pin "11") (pinfunction "DCD_11") (pintype "output"))
    )
    (net (code "71") (name "unconnected-(U2-DTR-Pad9)") (class "Default")
      (node (ref "U2") (pin "9") (pinfunction "DTR_9") (pintype "input"))
    )
    (net (code "72") (name "unconnected-(U2-GPIO17-Pad44)") (class "Default")
      (node (ref "U2") (pin "44") (pinfunction "GPIO17_44") (pintype "bidirectional"))
    )
    (net (code "73") (name "unconnected-(U2-GPIO19-Pad43)") (class "Default")
      (node (ref "U2") (pin "43") (pinfunction "GPIO19_43") (pintype "bidirectional"))
    )
    (net (code "74") (name "unconnected-(U2-KBC0-Pad62)") (class "Default")
      (node (ref "U2") (pin "62") (pinfunction "KBC0_62") (pintype "input"))
    )
    (net (code "75") (name "unconnected-(U2-KBC1-Pad61)") (class "Default")
      (node (ref "U2") (pin "61") (pinfunction "KBC1_61") (pintype "input"))
    )
    (net (code "76") (name "unconnected-(U2-KBC2-Pad60)") (class "Default")
      (node (ref "U2") (pin "60") (pinfunction "KBC2_60") (pintype "input"))
    )
    (net (code "77") (name "unconnected-(U2-KBC3-Pad59)") (class "Default")
      (node (ref "U2") (pin "59") (pinfunction "KBC3_59") (pintype "input"))
    )
    (net (code "78") (name "unconnected-(U2-KBR0-Pad58)") (class "Default")
      (node (ref "U2") (pin "58") (pinfunction "KBR0_58") (pintype "output"))
    )
    (net (code "79") (name "unconnected-(U2-KBR1-Pad57)") (class "Default")
      (node (ref "U2") (pin "57") (pinfunction "KBR1_57") (pintype "output"))
    )
    (net (code "80") (name "unconnected-(U2-KBR2-Pad56)") (class "Default")
      (node (ref "U2") (pin "56") (pinfunction "KBR2_56") (pintype "output"))
    )
    (net (code "81") (name "unconnected-(U2-KBR3-Pad55)") (class "Default")
      (node (ref "U2") (pin "55") (pinfunction "KBR3_55") (pintype "output"))
    )
    (net (code "82") (name "unconnected-(U2-MIC1N-Pad20)") (class "Default")
      (node (ref "U2") (pin "20") (pinfunction "MIC1N_20") (pintype "input"))
    )
    (net (code "83") (name "unconnected-(U2-MIC1P-Pad19)") (class "Default")
      (node (ref "U2") (pin "19") (pinfunction "MIC1P_19") (pintype "input"))
    )
    (net (code "84") (name "unconnected-(U2-NETLIGHT-Pad50)") (class "Default")
      (node (ref "U2") (pin "50") (pinfunction "NETLIGHT_50") (pintype "output"))
    )
    (net (code "85") (name "unconnected-(U2-PCM_CLK-Pad46)") (class "Default")
      (node (ref "U2") (pin "46") (pinfunction "PCM_CLK_46") (pintype "input"))
    )
    (net (code "86") (name "unconnected-(U2-PCM_IN-Pad47)") (class "Default")
      (node (ref "U2") (pin "47") (pinfunction "PCM_IN_47") (pintype "input"))
    )
    (net (code "87") (name "unconnected-(U2-PCM_OUT-Pad48)") (class "Default")
      (node (ref "U2") (pin "48") (pinfunction "PCM_OUT_48") (pintype "output"))
    )
    (net (code "88") (name "unconnected-(U2-PCM_SYNC-Pad45)") (class "Default")
      (node (ref "U2") (pin "45") (pinfunction "PCM_SYNC_45") (pintype "output"))
    )
    (net (code "89") (name "unconnected-(U2-PWM1-Pad42)") (class "Default")
      (node (ref "U2") (pin "42") (pinfunction "PWM1_42") (pintype "output"))
    )
    (net (code "90") (name "unconnected-(U2-PWM2-Pad41)") (class "Default")
      (node (ref "U2") (pin "41") (pinfunction "PWM2_41") (pintype "output"))
    )
    (net (code "91") (name "unconnected-(U2-RFSYNC-Pad63)") (class "Default")
      (node (ref "U2") (pin "63") (pinfunction "RFSYNC_63") (pintype "output"))
    )
    (net (code "92") (name "unconnected-(U2-RI-Pad10)") (class "Default")
      (node (ref "U2") (pin "10") (pinfunction "RI_10") (pintype "output"))
    )
    (net (code "93") (name "unconnected-(U2-RTS-Pad13)") (class "Default")
      (node (ref "U2") (pin "13") (pinfunction "RTS_13") (pintype "input"))
    )
    (net (code "94") (name "unconnected-(U2-SCL-Pad39)") (class "Default")
      (node (ref "U2") (pin "39") (pinfunction "SCL_39") (pintype "input"))
    )
    (net (code "95") (name "unconnected-(U2-SDA-Pad38)") (class "Default")
      (node (ref "U2") (pin "38") (pinfunction "SDA_38") (pintype "bidirectional"))
    )
    (net (code "96") (name "unconnected-(U2-SIM_DET-Pad33)") (class "Default")
      (node (ref "U2") (pin "33") (pinfunction "SIM_DET_33") (pintype "input"))
    )
    (net (code "97") (name "unconnected-(U2-SPK1N-Pad22)") (class "Default")
      (node (ref "U2") (pin "22") (pinfunction "SPK1N_22") (pintype "output"))
    )
    (net (code "98") (name "unconnected-(U2-SPK1P-Pad21)") (class "Default")
      (node (ref "U2") (pin "21") (pinfunction "SPK1P_21") (pintype "output"))
    )
    (net (code "99") (name "unconnected-(U2-STATUS-Pad49)") (class "Default")
      (node (ref "U2") (pin "49") (pinfunction "STATUS_49") (pintype "output"))
    )
    (net (code "100") (name "unconnected-(U2-USB_DN-Pad27)") (class "Default")
      (node (ref "U2") (pin "27") (pinfunction "USB_DN_27") (pintype "bidirectional"))
    )
    (net (code "101") (name "unconnected-(U2-USB_DP-Pad26)") (class "Default")
      (node (ref "U2") (pin "26") (pinfunction "USB_DP_26") (pintype "bidirectional"))
    )
    (net (code "102") (name "unconnected-(U2-VCHG-Pad25)") (class "Default")
      (node (ref "U2") (pin "25") (pinfunction "VCHG_25") (pintype "input"))
    )
    (net (code "103") (name "unconnected-(U2-VDD_EXT-Pad7)") (class "Default")
      (node (ref "U2") (pin "7") (pinfunction "VDD_EXT_7") (pintype "output"))
    )
  )
)
